# meter.net
KiCad netlist of a schematic drawn in EAGLE
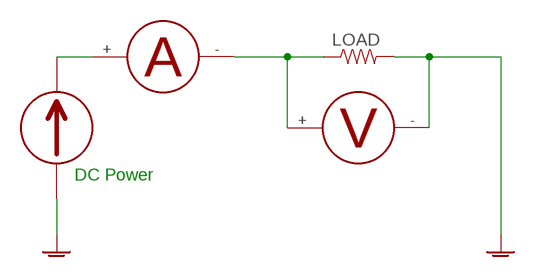
[diagram p0: schematic, sheet 1]

(export (version "E")
  (design (tool "Eeschema 10.0.6"))
  (components
    (comp (ref "DC_POEWR")
      (value "DCPOWER")
      (footprint "eagle-import:PS12")
      (libsource (lib "eagle-import") (part "DCPOWER"))
    )
    (comp (ref "LOAD")
      (value "RESISTORPTH-1/4W")
      (footprint "eagle-import:AXIAL-0.4")
      (libsource (lib "eagle-import") (part "RESISTORPTH-1/4W"))
    )
    (comp (ref "U$1")
      (value "AMMETER")
      (footprint "eagle-import:METER")
      (libsource (lib "eagle-import") (part "AMMETER"))
    )
    (comp (ref "U$2")
      (value "VOLTMETER")
      (footprint "eagle-import:METER")
      (libsource (lib "eagle-import") (part "VOLTMETER"))
    )
  )
  (nets
    (net (code "1") (name "AGND") (class "Default")
      (node (ref "DC_POEWR") (pin "P$1") (pinfunction "VGND_P$1") (pintype "output"))
      (node (ref "LOAD") (pin "P$2") (pinfunction "2_P$2") (pintype "passive"))
      (node (ref "U$2") (pin "-") (pinfunction "P$2_-") (pintype "input"))
    )
    (net (code "2") (name "Net-(DC_POEWR-VOUT)") (class "Default")
      (node (ref "DC_POEWR") (pin "P$2") (pinfunction "VOUT_P$2") (pintype "output"))
      (node (ref "U$1") (pin "+") (pinfunction "P$1_+") (pintype "input"))
    )
    (net (code "3") (name "Net-(LOAD-1)") (class "Default")
      (node (ref "LOAD") (pin "P$1") (pinfunction "1_P$1") (pintype "passive"))
      (node (ref "U$1") (pin "-") (pinfunction "P$2_-") (pintype "input"))
      (node (ref "U$2") (pin "+") (pinfunction "P$1_+") (pintype "input"))
    )
  )
)
